# bandpass_40m_v2.net
KiCad netlist of a schematic drawn in EAGLE
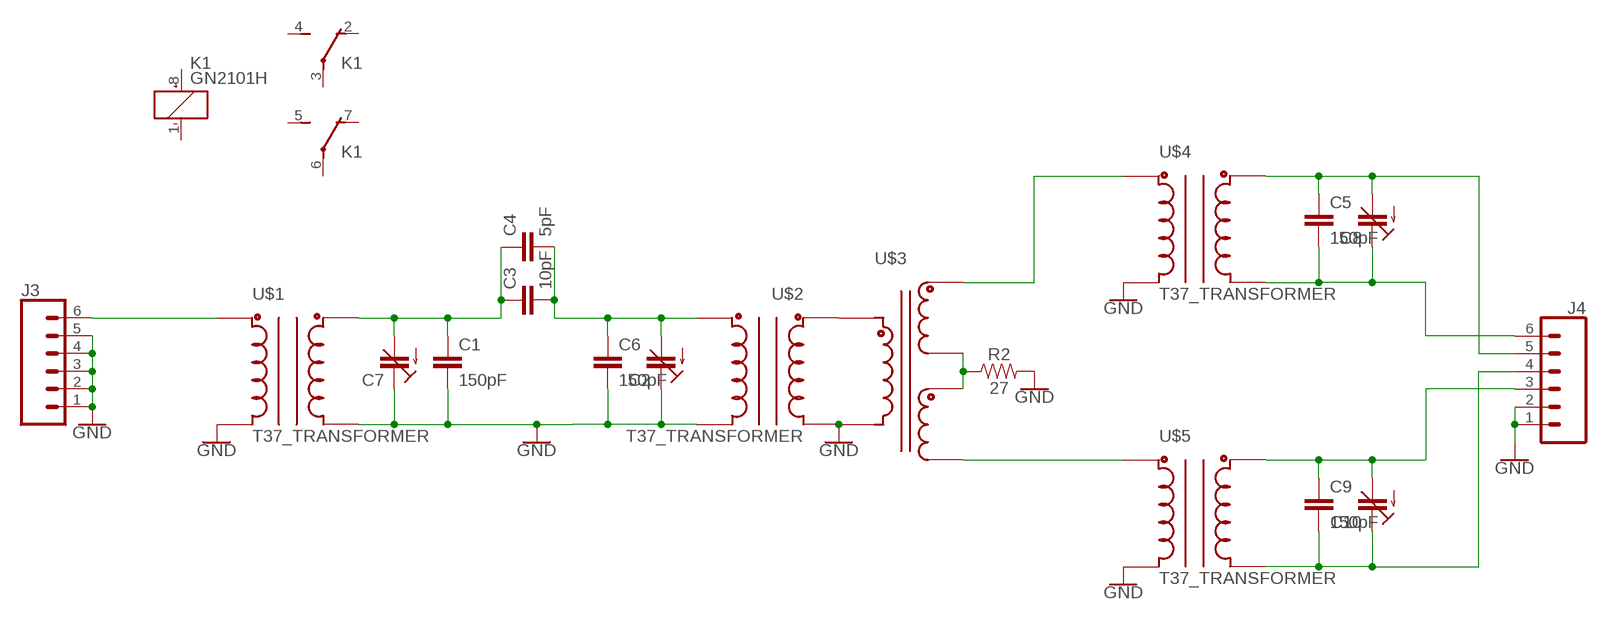
[diagram p0: schematic, sheet 1]

(export (version "E")
  (design (tool "Eeschema 10.0.6"))
  (components
    (comp (ref "C1")
      (value "150pF")
      (footprint "eagle-import:C5B3.5")
      (libsource (lib "eagle-import") (part "C5/3.5"))
    )
    (comp (ref "C2")
      (value "C-TRIMMTZ03")
      (footprint "eagle-import:CTRIMTZ03")
      (libsource (lib "eagle-import") (part "C-TRIMMTZ03"))
    )
    (comp (ref "C3")
      (value "10pF")
      (footprint "eagle-import:C5B3.5")
      (libsource (lib "eagle-import") (part "C5/3.5"))
    )
    (comp (ref "C4")
      (value "5pF")
      (footprint "eagle-import:C5B3.5")
      (libsource (lib "eagle-import") (part "C5/3.5"))
    )
    (comp (ref "C5")
      (value "150pF")
      (footprint "eagle-import:C5B3.5")
      (libsource (lib "eagle-import") (part "C5/3.5"))
    )
    (comp (ref "C6")
      (value "150pF")
      (footprint "eagle-import:C5B3.5")
      (libsource (lib "eagle-import") (part "C5/3.5"))
    )
    (comp (ref "C7")
      (value "C-TRIMMTZ03")
      (footprint "eagle-import:CTRIMTZ03")
      (libsource (lib "eagle-import") (part "C-TRIMMTZ03"))
    )
    (comp (ref "C8")
      (value "C-TRIMMTZ03")
      (footprint "eagle-import:CTRIMTZ03")
      (libsource (lib "eagle-import") (part "C-TRIMMTZ03"))
    )
    (comp (ref "C9")
      (value "150pF")
      (footprint "eagle-import:C5B3.5")
      (libsource (lib "eagle-import") (part "C5/3.5"))
    )
    (comp (ref "C10")
      (value "C-TRIMMTZ03")
      (footprint "eagle-import:CTRIMTZ03")
      (libsource (lib "eagle-import") (part "C-TRIMMTZ03"))
    )
    (comp (ref "J3")
      (value "CONN_06SILK_FEMALE_PTH")
      (footprint "eagle-import:1X06")
      (libsource (lib "eagle-import") (part "CONN_06SILK_FEMALE_PTH"))
    )
    (comp (ref "J4")
      (value "CONN_06SILK_FEMALE_PTH")
      (footprint "eagle-import:1X06")
      (libsource (lib "eagle-import") (part "CONN_06SILK_FEMALE_PTH"))
    )
    (comp (ref "K1")
      (value "GN2101H")
      (footprint "eagle-import:GN")
      (libsource (lib "eagle-import") (part "GN?2101H"))
    )
    (comp (ref "R2")
      (value "27")
      (footprint "eagle-import:AXIAL-0.3")
      (libsource (lib "eagle-import") (part "1KOHM-HORIZ-1/4W-1%"))
    )
    (comp (ref "U$1")
      (value "T37_TRANSFORMER")
      (footprint "eagle-import:T37_TRANSFORMER")
      (libsource (lib "eagle-import") (part "T37_TRANSFORMER"))
    )
    (comp (ref "U$2")
      (value "T37_TRANSFORMER")
      (footprint "eagle-import:T37_TRANSFORMER")
      (libsource (lib "eagle-import") (part "T37_TRANSFORMER"))
    )
    (comp (ref "U$3")
      (value "T50_SPLITTER")
      (footprint "eagle-import:T50_SPLITTER")
      (libsource (lib "eagle-import") (part "T50_SPLITTER"))
    )
    (comp (ref "U$4")
      (value "T37_TRANSFORMER")
      (footprint "eagle-import:T37_TRANSFORMER")
      (libsource (lib "eagle-import") (part "T37_TRANSFORMER"))
    )
    (comp (ref "U$5")
      (value "T37_TRANSFORMER")
      (footprint "eagle-import:T37_TRANSFORMER")
      (libsource (lib "eagle-import") (part "T37_TRANSFORMER"))
    )
  )
  (nets
    (net (code "1") (name "GND") (class "Default")
      (node (ref "C1") (pin "2") (pinfunction "2_2") (pintype "passive"))
      (node (ref "C2") (pin "1") (pinfunction "E_1") (pintype "passive"))
      (node (ref "C6") (pin "2") (pinfunction "2_2") (pintype "passive"))
      (node (ref "C7") (pin "1") (pinfunction "E_1") (pintype "passive"))
      (node (ref "J3") (pin "1") (pinfunction "1_1") (pintype "passive"))
      (node (ref "J3") (pin "2") (pinfunction "2_2") (pintype "passive"))
      (node (ref "J3") (pin "3") (pinfunction "3_3") (pintype "passive"))
      (node (ref "J3") (pin "4") (pinfunction "4_4") (pintype "passive"))
      (node (ref "J3") (pin "5") (pinfunction "5_5") (pintype "passive"))
      (node (ref "J4") (pin "1") (pinfunction "1_1") (pintype "passive"))
      (node (ref "J4") (pin "2") (pinfunction "2_2") (pintype "passive"))
      (node (ref "R2") (pin "P$2") (pinfunction "2_P$2") (pintype "passive"))
      (node (ref "U$1") (pin "C1A") (pinfunction "C1A_C1A") (pintype "bidirectional"))
      (node (ref "U$1") (pin "C2A") (pinfunction "C2A_C2A") (pintype "bidirectional"))
      (node (ref "U$2") (pin "C1A") (pinfunction "C1A_C1A") (pintype "bidirectional"))
      (node (ref "U$2") (pin "C2A") (pinfunction "C2A_C2A") (pintype "bidirectional"))
      (node (ref "U$3") (pin "C1A") (pinfunction "C1A_C1A") (pintype "bidirectional"))
      (node (ref "U$4") (pin "C1A") (pinfunction "C1A_C1A") (pintype "bidirectional"))
      (node (ref "U$5") (pin "C1A") (pinfunction "C1A_C1A") (pintype "bidirectional"))
    )
    (net (code "2") (name "Net-(C2-A)") (class "Default")
      (node (ref "C2") (pin "2") (pinfunction "A_2") (pintype "passive"))
      (node (ref "C3") (pin "2") (pinfunction "2_2") (pintype "passive"))
      (node (ref "C4") (pin "2") (pinfunction "2_2") (pintype "passive"))
      (node (ref "C6") (pin "1") (pinfunction "1_1") (pintype "passive"))
      (node (ref "U$2") (pin "C2B") (pinfunction "C2B_C2B") (pintype "bidirectional"))
    )
    (net (code "3") (name "Net-(C7-A)") (class "Default")
      (node (ref "C1") (pin "1") (pinfunction "1_1") (pintype "passive"))
      (node (ref "C3") (pin "1") (pinfunction "1_1") (pintype "passive"))
      (node (ref "C4") (pin "1") (pinfunction "1_1") (pintype "passive"))
      (node (ref "C7") (pin "2") (pinfunction "A_2") (pintype "passive"))
      (node (ref "U$1") (pin "C2B") (pinfunction "C2B_C2B") (pintype "bidirectional"))
    )
    (net (code "4") (name "Net-(C8-A)") (class "Default")
      (node (ref "C5") (pin "1") (pinfunction "1_1") (pintype "passive"))
      (node (ref "C8") (pin "2") (pinfunction "A_2") (pintype "passive"))
      (node (ref "J4") (pin "5") (pinfunction "5_5") (pintype "passive"))
      (node (ref "U$4") (pin "C2B") (pinfunction "C2B_C2B") (pintype "bidirectional"))
    )
    (net (code "5") (name "Net-(C8-E)") (class "Default")
      (node (ref "C5") (pin "2") (pinfunction "2_2") (pintype "passive"))
      (node (ref "C8") (pin "1") (pinfunction "E_1") (pintype "passive"))
      (node (ref "J4") (pin "6") (pinfunction "6_6") (pintype "passive"))
      (node (ref "U$4") (pin "C2A") (pinfunction "C2A_C2A") (pintype "bidirectional"))
    )
    (net (code "6") (name "Net-(C10-A)") (class "Default")
      (node (ref "C10") (pin "2") (pinfunction "A_2") (pintype "passive"))
      (node (ref "C9") (pin "1") (pinfunction "1_1") (pintype "passive"))
      (node (ref "J4") (pin "3") (pinfunction "3_3") (pintype "passive"))
      (node (ref "U$5") (pin "C2B") (pinfunction "C2B_C2B") (pintype "bidirectional"))
    )
    (net (code "7") (name "Net-(C10-E)") (class "Default")
      (node (ref "C10") (pin "1") (pinfunction "E_1") (pintype "passive"))
      (node (ref "C9") (pin "2") (pinfunction "2_2") (pintype "passive"))
      (node (ref "J4") (pin "4") (pinfunction "4_4") (pintype "passive"))
      (node (ref "U$5") (pin "C2A") (pinfunction "C2A_C2A") (pintype "bidirectional"))
    )
    (net (code "8") (name "Net-(J3-Pad6)") (class "Default")
      (node (ref "J3") (pin "6") (pinfunction "6_6") (pintype "passive"))
      (node (ref "U$1") (pin "C1B") (pinfunction "C1B_C1B") (pintype "bidirectional"))
    )
    (net (code "9") (name "Net-(R2-1)") (class "Default")
      (node (ref "R2") (pin "P$1") (pinfunction "1_P$1") (pintype "passive"))
      (node (ref "U$3") (pin "C2A") (pinfunction "C3B_C2A") (pintype "bidirectional"))
      (node (ref "U$3") (pin "C3A") (pinfunction "C2A_C3A") (pintype "bidirectional"))
    )
    (net (code "10") (name "Net-(U$2-PadC1B)") (class "Default")
      (node (ref "U$2") (pin "C1B") (pinfunction "C1B_C1B") (pintype "bidirectional"))
      (node (ref "U$3") (pin "C1B") (pinfunction "C1B_C1B") (pintype "bidirectional"))
    )
    (net (code "11") (name "Net-(U$3-C2B)") (class "Default")
      (node (ref "U$3") (pin "C3B") (pinfunction "C2B_C3B") (pintype "bidirectional"))
      (node (ref "U$4") (pin "C1B") (pinfunction "C1B_C1B") (pintype "bidirectional"))
    )
    (net (code "12") (name "Net-(U$3-C3A)") (class "Default")
      (node (ref "U$3") (pin "C2B") (pinfunction "C3A_C2B") (pintype "bidirectional"))
      (node (ref "U$5") (pin "C1B") (pinfunction "C1B_C1B") (pintype "bidirectional"))
    )
    (net (code "13") (name "unconnected-(K1A-+-Pad8)") (class "Default")
      (node (ref "K1") (pin "8") (pinfunction "+_8") (pintype "passive"))
    )
    (net (code "14") (name "unconnected-(K1A---Pad1)") (class "Default")
      (node (ref "K1") (pin "1") (pinfunction "-_1") (pintype "passive"))
    )
    (net (code "15") (name "unconnected-(K1B-O-Pad2)") (class "Default")
      (node (ref "K1") (pin "2") (pinfunction "O_2") (pintype "passive"))
    )
    (net (code "16") (name "unconnected-(K1B-P-Pad3)") (class "Default")
      (node (ref "K1") (pin "3") (pinfunction "P_3") (pintype "passive"))
    )
    (net (code "17") (name "unconnected-(K1B-S-Pad4)") (class "Default")
      (node (ref "K1") (pin "4") (pinfunction "S_4") (pintype "passive"))
    )
    (net (code "18") (name "unconnected-(K1C-O-Pad7)") (class "Default")
      (node (ref "K1") (pin "7") (pinfunction "O_7") (pintype "passive"))
    )
    (net (code "19") (name "unconnected-(K1C-P-Pad6)") (class "Default")
      (node (ref "K1") (pin "6") (pinfunction "P_6") (pintype "passive"))
    )
    (net (code "20") (name "unconnected-(K1C-S-Pad5)") (class "Default")
      (node (ref "K1") (pin "5") (pinfunction "S_5") (pintype "passive"))
    )
  )
)
